# PCBAv.net
KiCad netlist of a schematic drawn in EAGLE
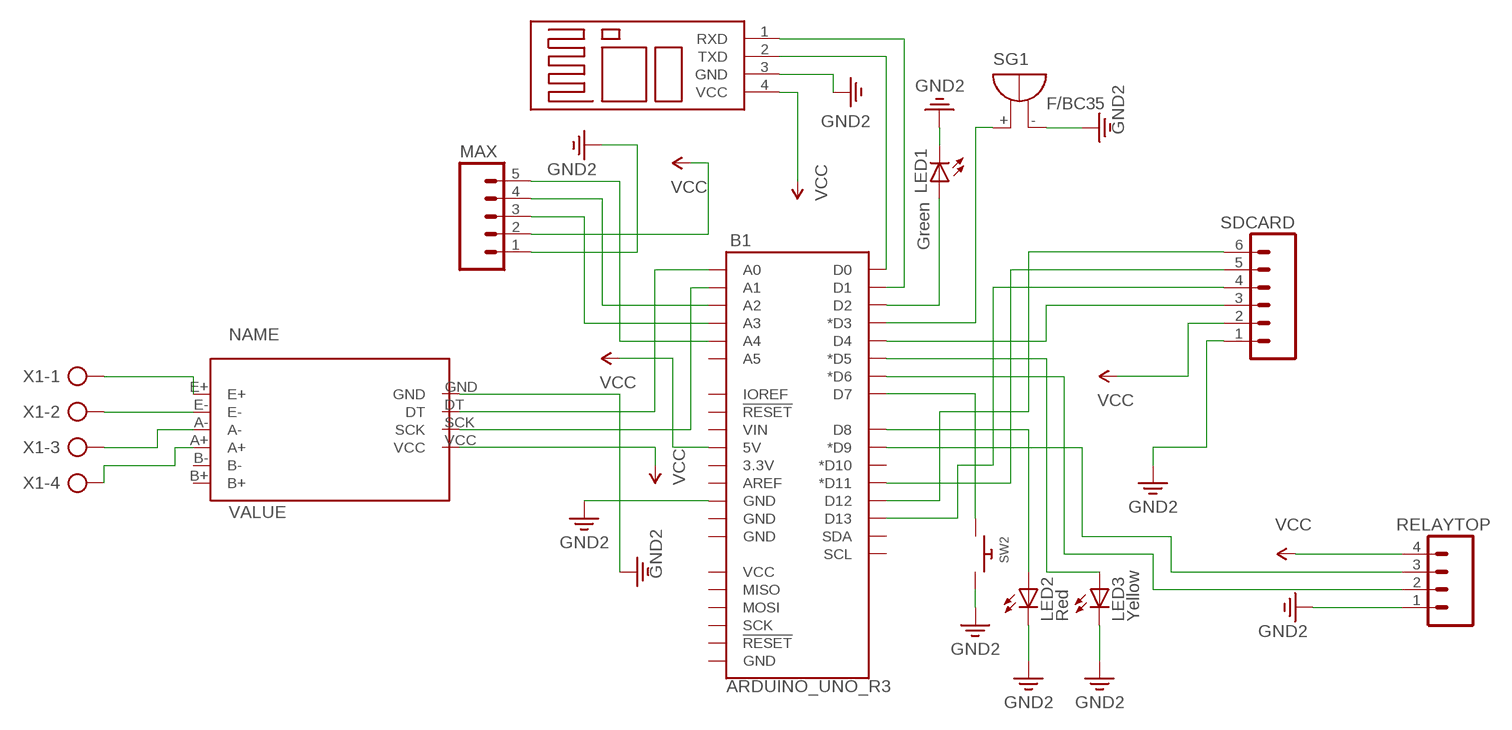
[diagram p0: schematic, sheet 1]

(export (version "E")
  (design (tool "Eeschema 10.0.6"))
  (components
    (comp (ref "B1")
      (value "ARDUINO_UNO_R3")
      (footprint "eagle-import:ARDUINO_R3")
      (libsource (lib "eagle-import") (part "ARDUINO_UNO_R3"))
    )
    (comp (ref "HC05")
      (value "BLUETOOTH")
      (footprint "eagle-import:BLUETOOTH")
      (libsource (lib "eagle-import") (part "BLUETOOTH"))
    )
    (comp (ref "LED1")
      (value "Green")
      (footprint "eagle-import:LED5MM")
      (libsource (lib "eagle-import") (part "LED5MM"))
    )
    (comp (ref "LED2")
      (value "Red")
      (footprint "eagle-import:LED5MM")
      (libsource (lib "eagle-import") (part "LED5MM"))
    )
    (comp (ref "LED3")
      (value "Yellow")
      (footprint "eagle-import:LED5MM")
      (libsource (lib "eagle-import") (part "LED5MM"))
    )
    (comp (ref "MAX")
      (value "M05")
      (footprint "eagle-import:05P")
      (libsource (lib "eagle-import") (part "M05"))
    )
    (comp (ref "RELAYTOP")
      (value "M04")
      (footprint "eagle-import:04P")
      (libsource (lib "eagle-import") (part "M04"))
    )
    (comp (ref "SDCARD")
      (value "M06")
      (footprint "eagle-import:06P")
      (libsource (lib "eagle-import") (part "M06"))
    )
    (comp (ref "SG1")
      (value "F/BC35")
      (footprint "eagle-import:F_BC35")
      (libsource (lib "eagle-import") (part "F/BC35"))
    )
    (comp (ref "SW2")
      (value "SWITCH_PUSHBUTTONEVQ-PE")
      (footprint "eagle-import:TACT_PANA-EVQ")
      (libsource (lib "eagle-import") (part "SWITCH_PUSHBUTTONEVQ-PE"))
    )
    (comp (ref "U$1")
      (value "HX711")
      (footprint "eagle-import:HX711")
      (libsource (lib "eagle-import") (part "HX711"))
    )
    (comp (ref "X1")
      (value "AK300/4")
      (footprint "eagle-import:AK300_4")
      (libsource (lib "eagle-import") (part "AK300/4"))
    )
  )
  (nets
    (net (code "1") (name "GND2") (class "Default")
      (node (ref "B1") (pin "GND@4") (pinfunction "GND_GND@4") (pintype "bidirectional"))
      (node (ref "HC05") (pin "3") (pinfunction "GND_3") (pintype "power_in"))
      (node (ref "LED1") (pin "K") (pinfunction "C_K") (pintype "passive"))
      (node (ref "LED2") (pin "K") (pinfunction "C_K") (pintype "passive"))
      (node (ref "LED3") (pin "K") (pinfunction "C_K") (pintype "passive"))
      (node (ref "MAX") (pin "1") (pinfunction "1_1") (pintype "passive"))
      (node (ref "RELAYTOP") (pin "1") (pinfunction "1_1") (pintype "passive"))
      (node (ref "SDCARD") (pin "1") (pinfunction "1_1") (pintype "passive"))
      (node (ref "SG1") (pin "-") (pinfunction "-_-") (pintype "passive"))
      (node (ref "SW2") (pin "P$2") (pinfunction "P$2_P$2") (pintype "passive"))
      (node (ref "U$1") (pin "GND") (pinfunction "GND_GND") (pintype "bidirectional"))
    )
    (net (code "2") (name "Net-(B1-*D3)") (class "Default")
      (node (ref "B1") (pin "D3") (pinfunction "*D3_D3") (pintype "bidirectional"))
      (node (ref "SG1") (pin "+") (pinfunction "+_+") (pintype "passive"))
    )
    (net (code "3") (name "Net-(B1-*D5)") (class "Default")
      (node (ref "B1") (pin "D5") (pinfunction "*D5_D5") (pintype "bidirectional"))
      (node (ref "LED3") (pin "A") (pinfunction "A_A") (pintype "passive"))
    )
    (net (code "4") (name "Net-(B1-*D6)") (class "Default")
      (node (ref "B1") (pin "D6") (pinfunction "*D6_D6") (pintype "bidirectional"))
      (node (ref "RELAYTOP") (pin "2") (pinfunction "2_2") (pintype "passive"))
    )
    (net (code "5") (name "Net-(B1-*D9)") (class "Default")
      (node (ref "B1") (pin "D9") (pinfunction "*D9_D9") (pintype "bidirectional"))
      (node (ref "RELAYTOP") (pin "3") (pinfunction "3_3") (pintype "passive"))
    )
    (net (code "6") (name "Net-(B1-*D11)") (class "Default")
      (node (ref "B1") (pin "D11") (pinfunction "*D11_D11") (pintype "bidirectional"))
      (node (ref "SDCARD") (pin "5") (pinfunction "5_5") (pintype "passive"))
    )
    (net (code "7") (name "Net-(B1-PadA0)") (class "Default")
      (node (ref "B1") (pin "A0") (pinfunction "A0_A0") (pintype "bidirectional"))
      (node (ref "U$1") (pin "DT") (pinfunction "DT_DT") (pintype "bidirectional"))
    )
    (net (code "8") (name "Net-(B1-PadA1)") (class "Default")
      (node (ref "B1") (pin "A1") (pinfunction "A1_A1") (pintype "bidirectional"))
      (node (ref "U$1") (pin "SCK") (pinfunction "SCK_SCK") (pintype "bidirectional"))
    )
    (net (code "9") (name "Net-(B1-PadA2)") (class "Default")
      (node (ref "B1") (pin "A2") (pinfunction "A2_A2") (pintype "bidirectional"))
      (node (ref "MAX") (pin "4") (pinfunction "4_4") (pintype "passive"))
    )
    (net (code "10") (name "Net-(B1-PadA3)") (class "Default")
      (node (ref "B1") (pin "A3") (pinfunction "A3_A3") (pintype "bidirectional"))
      (node (ref "MAX") (pin "3") (pinfunction "3_3") (pintype "passive"))
    )
    (net (code "11") (name "Net-(B1-PadA4)") (class "Default")
      (node (ref "B1") (pin "A4") (pinfunction "A4_A4") (pintype "bidirectional"))
      (node (ref "MAX") (pin "5") (pinfunction "5_5") (pintype "passive"))
    )
    (net (code "12") (name "Net-(B1-PadD2)") (class "Default")
      (node (ref "B1") (pin "D2") (pinfunction "D2_D2") (pintype "bidirectional"))
      (node (ref "LED1") (pin "A") (pinfunction "A_A") (pintype "passive"))
    )
    (net (code "13") (name "Net-(B1-PadD4)") (class "Default")
      (node (ref "B1") (pin "D4") (pinfunction "D4_D4") (pintype "bidirectional"))
      (node (ref "SDCARD") (pin "3") (pinfunction "3_3") (pintype "passive"))
    )
    (net (code "14") (name "Net-(B1-PadD7)") (class "Default")
      (node (ref "B1") (pin "D7") (pinfunction "D7_D7") (pintype "bidirectional"))
      (node (ref "SW2") (pin "P$1") (pinfunction "P$1_P$1") (pintype "passive"))
    )
    (net (code "15") (name "Net-(B1-PadD8)") (class "Default")
      (node (ref "B1") (pin "D8") (pinfunction "D8_D8") (pintype "bidirectional"))
      (node (ref "LED2") (pin "A") (pinfunction "A_A") (pintype "passive"))
    )
    (net (code "16") (name "Net-(B1-PadD12)") (class "Default")
      (node (ref "B1") (pin "D12") (pinfunction "D12_D12") (pintype "bidirectional"))
      (node (ref "SDCARD") (pin "6") (pinfunction "6_6") (pintype "passive"))
    )
    (net (code "17") (name "Net-(B1-PadD13)") (class "Default")
      (node (ref "B1") (pin "D13") (pinfunction "D13_D13") (pintype "bidirectional"))
      (node (ref "SDCARD") (pin "4") (pinfunction "4_4") (pintype "passive"))
    )
    (net (code "18") (name "Net-(HC05-RXD)") (class "Default")
      (node (ref "B1") (pin "D1") (pinfunction "D1_D1") (pintype "bidirectional"))
      (node (ref "HC05") (pin "1") (pinfunction "RXD_1") (pintype "bidirectional"))
    )
    (net (code "19") (name "Net-(HC05-TXD)") (class "Default")
      (node (ref "B1") (pin "D0") (pinfunction "D0_D0") (pintype "bidirectional"))
      (node (ref "HC05") (pin "2") (pinfunction "TXD_2") (pintype "bidirectional"))
    )
    (net (code "20") (name "Net-(X1A-KL)") (class "Default")
      (node (ref "U$1") (pin "E+") (pinfunction "E+_E+") (pintype "bidirectional"))
      (node (ref "X1") (pin "1") (pinfunction "KL_1") (pintype "passive"))
    )
    (net (code "21") (name "Net-(X1B-KL)") (class "Default")
      (node (ref "U$1") (pin "E-") (pinfunction "E-_E-") (pintype "bidirectional"))
      (node (ref "X1") (pin "2") (pinfunction "KL_2") (pintype "passive"))
    )
    (net (code "22") (name "Net-(X1C-KL)") (class "Default")
      (node (ref "U$1") (pin "A-") (pinfunction "A-_A-") (pintype "bidirectional"))
      (node (ref "X1") (pin "3") (pinfunction "KL_3") (pintype "passive"))
    )
    (net (code "23") (name "Net-(X1D-KL)") (class "Default")
      (node (ref "U$1") (pin "A+") (pinfunction "A+_A+") (pintype "bidirectional"))
      (node (ref "X1") (pin "4") (pinfunction "KL_4") (pintype "passive"))
    )
    (net (code "24") (name "VCC") (class "Default")
      (node (ref "B1") (pin "5V") (pinfunction "5V_5V") (pintype "bidirectional"))
      (node (ref "HC05") (pin "4") (pinfunction "VCC_4") (pintype "power_in"))
      (node (ref "MAX") (pin "2") (pinfunction "2_2") (pintype "passive"))
      (node (ref "RELAYTOP") (pin "4") (pinfunction "4_4") (pintype "passive"))
      (node (ref "SDCARD") (pin "2") (pinfunction "2_2") (pintype "passive"))
      (node (ref "U$1") (pin "VCC") (pinfunction "VCC_VCC") (pintype "bidirectional"))
    )
    (net (code "25") (name "unconnected-(B1-*D10-PadD10)") (class "Default")
      (node (ref "B1") (pin "D10") (pinfunction "*D10_D10") (pintype "bidirectional"))
    )
    (net (code "26") (name "unconnected-(B1-GND-PadGND@1)") (class "Default")
      (node (ref "B1") (pin "GND@1") (pinfunction "GND_GND@1") (pintype "bidirectional"))
    )
    (net (code "27") (name "unconnected-(B1-GND-PadGND@2)") (class "Default")
      (node (ref "B1") (pin "GND@2") (pinfunction "GND_GND@2") (pintype "bidirectional"))
    )
    (net (code "28") (name "unconnected-(B1-GND-PadGND@3)") (class "Default")
      (node (ref "B1") (pin "GND@3") (pinfunction "GND_GND@3") (pintype "bidirectional"))
    )
    (net (code "29") (name "unconnected-(B1-Pad3.3V)") (class "Default")
      (node (ref "B1") (pin "3.3V") (pinfunction "3.3V_3.3V") (pintype "bidirectional"))
    )
    (net (code "30") (name "unconnected-(B1-PadA5)") (class "Default")
      (node (ref "B1") (pin "A5") (pinfunction "A5_A5") (pintype "bidirectional"))
    )
    (net (code "31") (name "unconnected-(B1-PadAREF)") (class "Default")
      (node (ref "B1") (pin "AREF") (pinfunction "AREF_AREF") (pintype "bidirectional"))
    )
    (net (code "32") (name "unconnected-(B1-PadIOREF)") (class "Default")
      (node (ref "B1") (pin "IOREF") (pinfunction "IOREF_IOREF") (pintype "bidirectional"))
    )
    (net (code "33") (name "unconnected-(B1-PadMISO)") (class "Default")
      (node (ref "B1") (pin "MISO") (pinfunction "MISO_MISO") (pintype "bidirectional"))
    )
    (net (code "34") (name "unconnected-(B1-PadMOSI)") (class "Default")
      (node (ref "B1") (pin "MOSI") (pinfunction "MOSI_MOSI") (pintype "bidirectional"))
    )
    (net (code "35") (name "unconnected-(B1-PadSCK)") (class "Default")
      (node (ref "B1") (pin "SCK") (pinfunction "SCK_SCK") (pintype "bidirectional"))
    )
    (net (code "36") (name "unconnected-(B1-PadSCL)") (class "Default")
      (node (ref "B1") (pin "SCL") (pinfunction "SCL_SCL") (pintype "bidirectional"))
    )
    (net (code "37") (name "unconnected-(B1-PadSDA)") (class "Default")
      (node (ref "B1") (pin "SDA") (pinfunction "SDA_SDA") (pintype "bidirectional"))
    )
    (net (code "38") (name "unconnected-(B1-PadVCC)") (class "Default")
      (node (ref "B1") (pin "VCC") (pinfunction "VCC_VCC") (pintype "bidirectional"))
    )
    (net (code "39") (name "unconnected-(B1-PadVIN)") (class "Default")
      (node (ref "B1") (pin "VIN") (pinfunction "VIN_VIN") (pintype "bidirectional"))
    )
    (net (code "40") (name "unconnected-(B1-~{RESET}-PadRESET@1)") (class "Default")
      (node (ref "B1") (pin "RESET@1") (pinfunction "~{RESET}_RESET@1") (pintype "bidirectional"))
    )
    (net (code "41") (name "unconnected-(B1-~{RESET}-PadRESET@2)") (class "Default")
      (node (ref "B1") (pin "RESET@2") (pinfunction "~{RESET}_RESET@2") (pintype "bidirectional"))
    )
    (net (code "42") (name "unconnected-(U$1-PadB+)") (class "Default")
      (node (ref "U$1") (pin "B+") (pinfunction "B+_B+") (pintype "bidirectional"))
    )
    (net (code "43") (name "unconnected-(U$1-PadB-)") (class "Default")
      (node (ref "U$1") (pin "B-") (pinfunction "B-_B-") (pintype "bidirectional"))
    )
  )
)
